# mp3412-boost-driver-13mm-mk-1_0.net
KiCad netlist of a schematic drawn in EAGLE
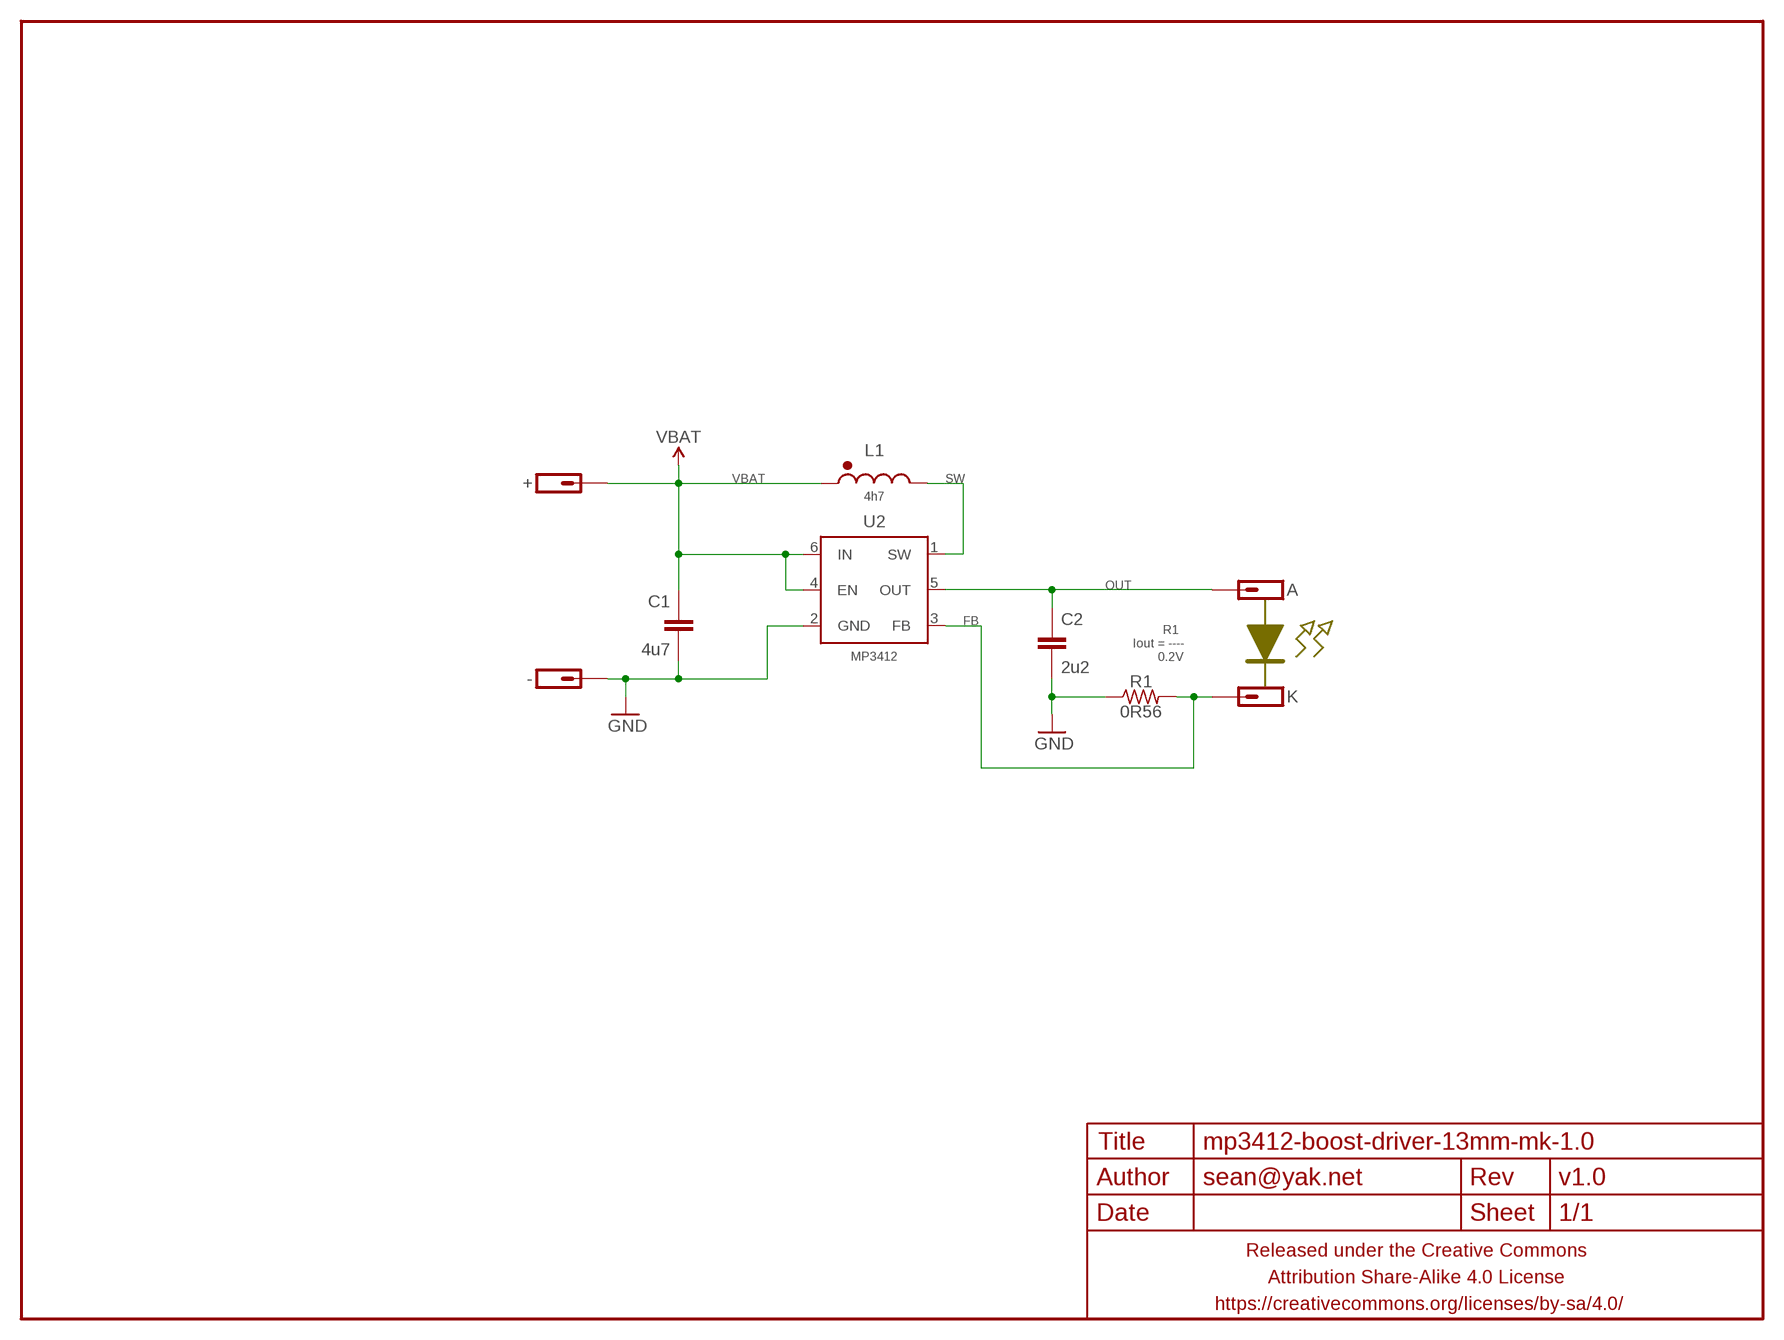
[diagram p0: schematic, sheet 1]

(export (version "E")
  (design (tool "Eeschema 10.0.6"))
  (components
    (comp (ref "+")
      (value "M01NOT-A-VIA-NOPE")
      (footprint "eagle-import:1X01_NOSILK_NOSTOP")
      (libsource (lib "eagle-import") (part "M01NOT-A-VIA-NOPE"))
    )
    (comp (ref "-")
      (value "M01NOT-A-VIA-NOPE")
      (footprint "eagle-import:1X01_NOSILK_NOSTOP")
      (libsource (lib "eagle-import") (part "M01NOT-A-VIA-NOPE"))
    )
    (comp (ref "A")
      (value "M01SMD_1.5X2MM")
      (footprint "eagle-import:1X01_1.5X2MM")
      (libsource (lib "eagle-import") (part "M01SMD_1.5X2MM"))
    )
    (comp (ref "C1")
      (value "4u7")
      (footprint "eagle-import:C0603-TIGHTER")
      (libsource (lib "eagle-import") (part "CAPACITOR-CERAMICC0603-TIGHTER"))
    )
    (comp (ref "C2")
      (value "2u2")
      (footprint "eagle-import:C0603-TIGHTER")
      (libsource (lib "eagle-import") (part "CAPACITOR-CERAMICC0603-TIGHTER"))
    )
    (comp (ref "FRAME1")
      (value "FRAME-LETTERNO_PACKAGE")
      (footprint "eagle-import:DUMMY")
      (fields (field (name "DESIGNER") "sean@yak.net") (field (name "VERSION") "v1.0"))
      (libsource (lib "eagle-import") (part "FRAME-LETTERNO_PACKAGE"))
    )
    (comp (ref "K")
      (value "M01SMD_1.5X2MM")
      (footprint "eagle-import:1X01_1.5X2MM")
      (libsource (lib "eagle-import") (part "M01SMD_1.5X2MM"))
    )
    (comp (ref "L1")
      (value "4h7")
      (footprint "eagle-import:EPL2014")
      (libsource (lib "eagle-import") (part "INDUCTOREPL2014"))
    )
    (comp (ref "R1")
      (value "0R56")
      (footprint "eagle-import:R0603-TIGHTER")
      (libsource (lib "eagle-import") (part "RESISTORR0603-TIGHTER"))
    )
    (comp (ref "U2")
      (value "MP3412")
      (footprint "eagle-import:TSOT-23-6")
      (libsource (lib "eagle-import") (part "MP3412"))
    )
  )
  (nets
    (net (code "1") (name "/FB") (class "Default")
      (node (ref "K") (pin "P$1") (pinfunction "1_P$1") (pintype "passive"))
      (node (ref "R1") (pin "2") (pinfunction "2_2") (pintype "passive"))
      (node (ref "U2") (pin "3") (pinfunction "FB_3") (pintype "bidirectional"))
    )
    (net (code "2") (name "/OUT") (class "Default")
      (node (ref "A") (pin "P$1") (pinfunction "1_P$1") (pintype "passive"))
      (node (ref "C2") (pin "1") (pinfunction "1_1") (pintype "passive"))
      (node (ref "U2") (pin "5") (pinfunction "OUT_5") (pintype "bidirectional"))
    )
    (net (code "3") (name "/SW") (class "Default")
      (node (ref "L1") (pin "P$2") (pinfunction "2_P$2") (pintype "passive"))
      (node (ref "U2") (pin "1") (pinfunction "SW_1") (pintype "bidirectional"))
    )
    (net (code "4") (name "GND") (class "Default")
      (node (ref "-") (pin "P$1") (pinfunction "1_P$1") (pintype "passive"))
      (node (ref "C1") (pin "2") (pinfunction "2_2") (pintype "passive"))
      (node (ref "C2") (pin "2") (pinfunction "2_2") (pintype "passive"))
      (node (ref "R1") (pin "1") (pinfunction "1_1") (pintype "passive"))
      (node (ref "U2") (pin "2") (pinfunction "GND_2") (pintype "bidirectional"))
    )
    (net (code "5") (name "VBAT") (class "Default")
      (node (ref "+") (pin "P$1") (pinfunction "1_P$1") (pintype "passive"))
      (node (ref "C1") (pin "1") (pinfunction "1_1") (pintype "passive"))
      (node (ref "L1") (pin "P$1") (pinfunction "1_P$1") (pintype "passive"))
      (node (ref "U2") (pin "4") (pinfunction "EN_4") (pintype "bidirectional"))
      (node (ref "U2") (pin "6") (pinfunction "IN_6") (pintype "bidirectional"))
    )
  )
)
